# SensorCircuit.net
KiCad netlist of a schematic drawn in Altium Designer
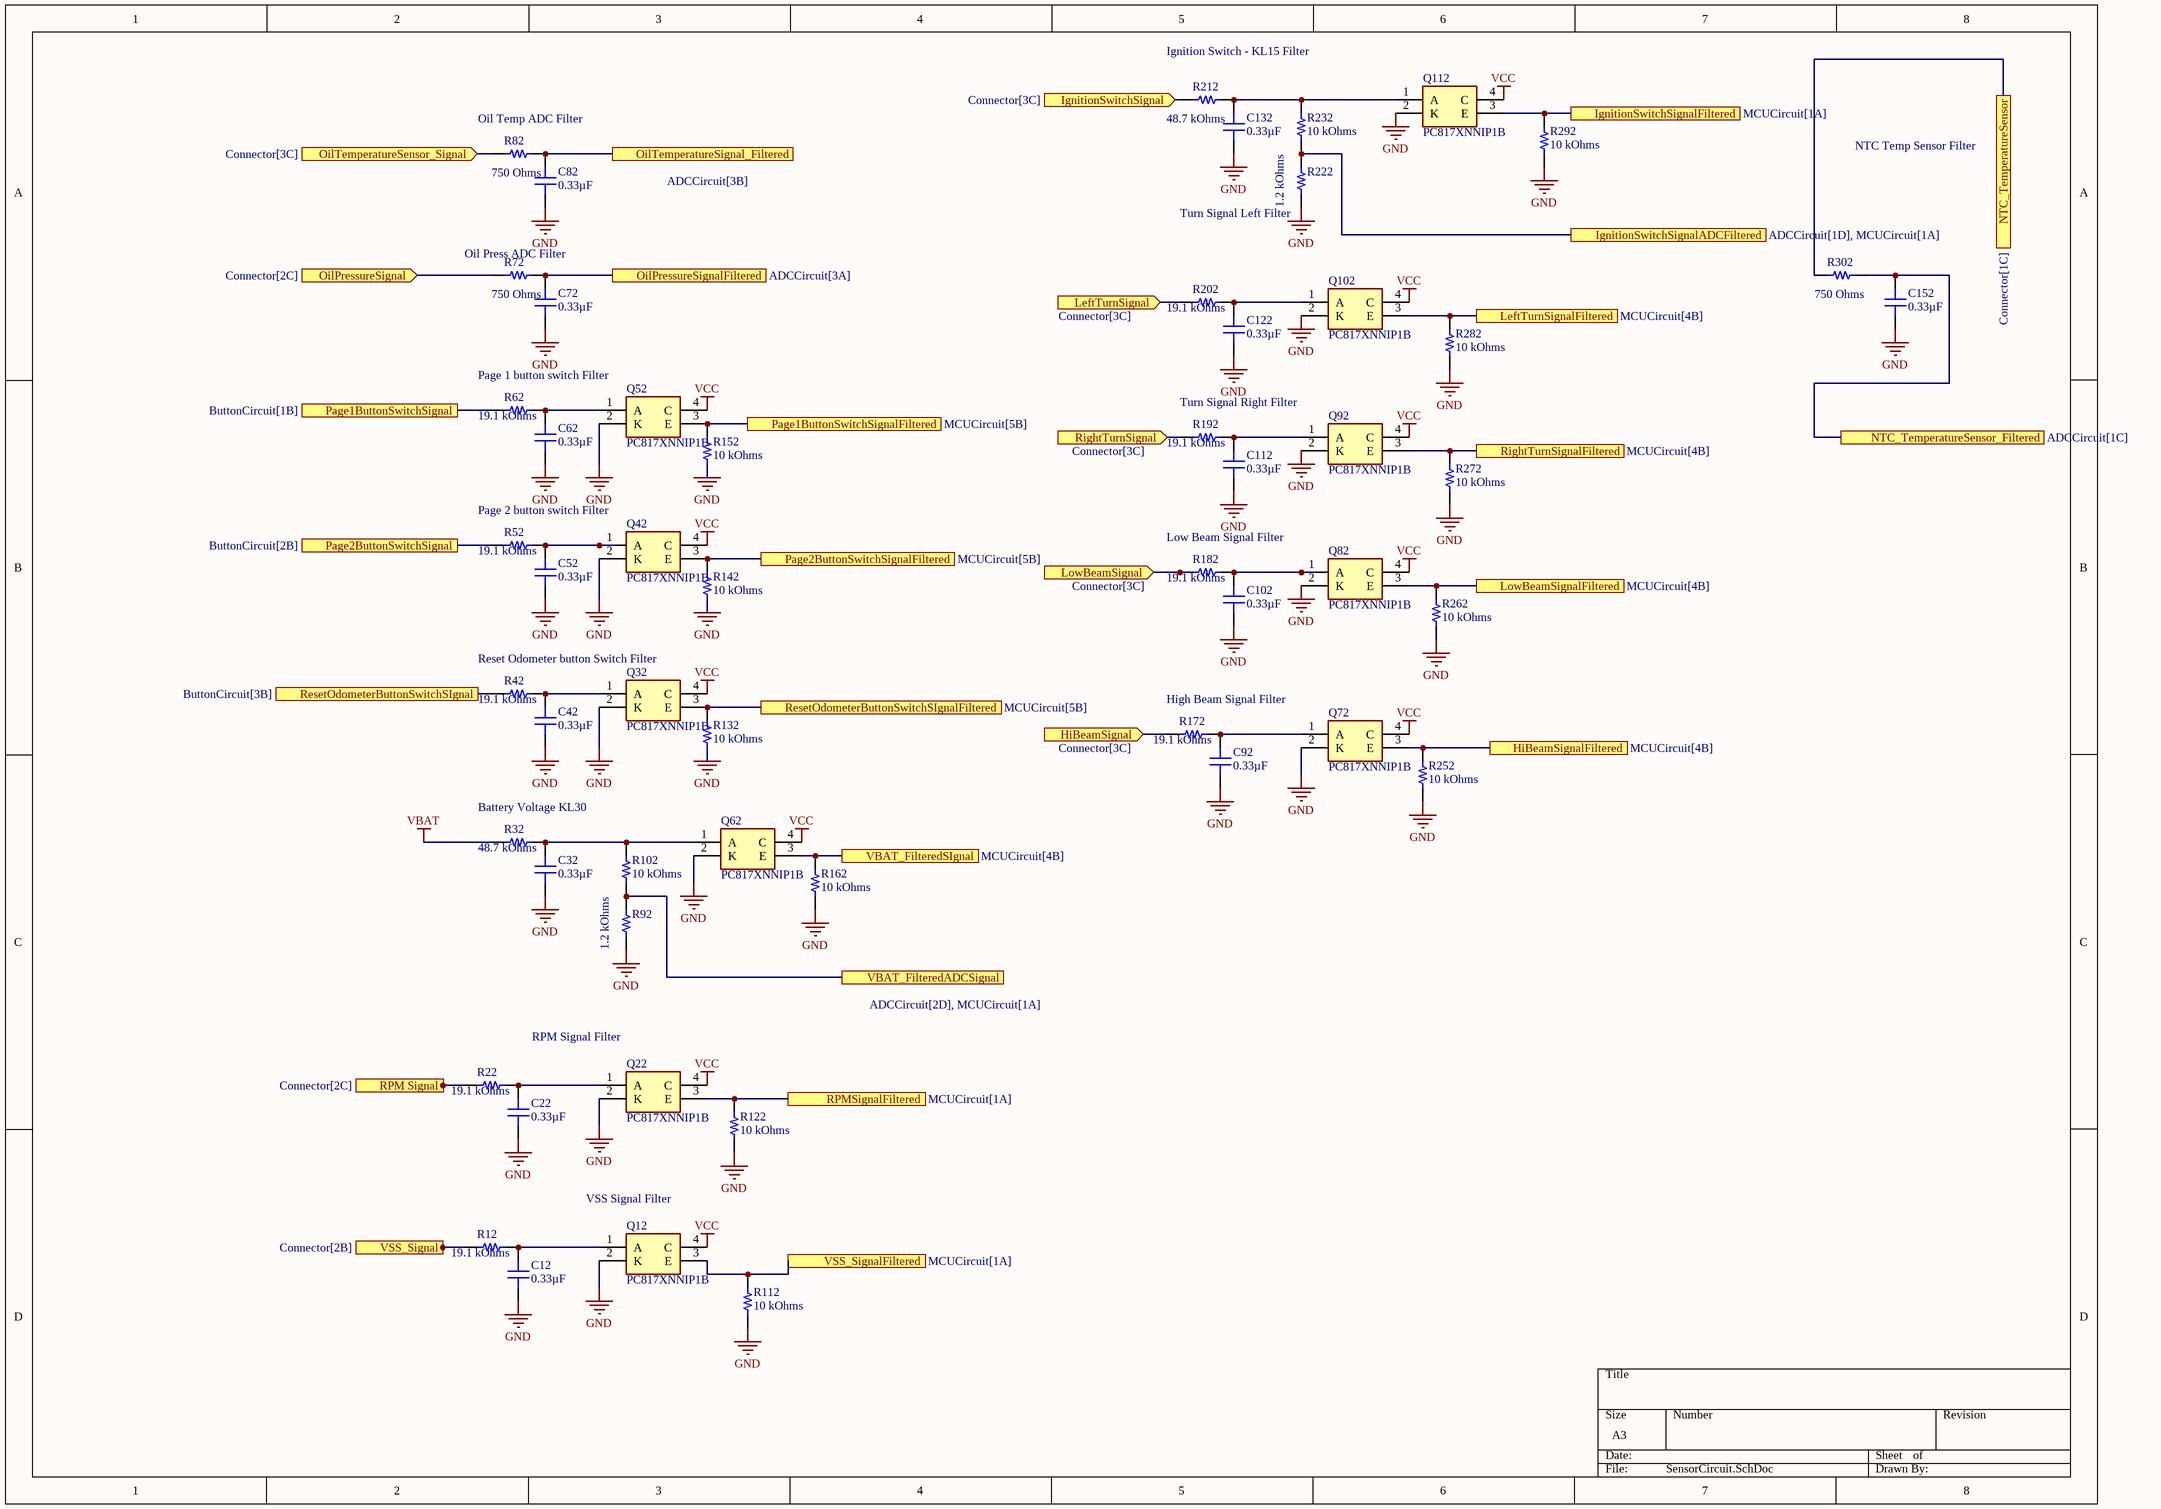
[diagram p0: SensorCircuit.SchDoc]

(export (version "E")
  (design (tool "Eeschema 10.0.6"))
  (components
    (comp (ref "C12")
      (value "0.33µF")
      (footprint "C0805")
      (description "CAP CER 0.33UF 16V X7R 0805")
      (fields (field (name "PART NUMBER") "0805YC334JAT2A") (field (name "MANUFACTURER") "AVX Corporation"))
      (libsource (lib "Celestial Altium Library - altium_library") (part "Capacitor"))
    )
    (comp (ref "C22")
      (value "0.33µF")
      (footprint "C0805")
      (description "CAP CER 0.33UF 16V X7R 0805")
      (fields (field (name "PART NUMBER") "0805YC334JAT2A") (field (name "MANUFACTURER") "AVX Corporation"))
      (libsource (lib "Celestial Altium Library - altium_library") (part "Capacitor"))
    )
    (comp (ref "C32")
      (value "0.33µF")
      (footprint "C0805")
      (description "CAP CER 0.33UF 16V X7R 0805")
      (fields (field (name "PART NUMBER") "0805YC334JAT2A") (field (name "MANUFACTURER") "AVX Corporation"))
      (libsource (lib "Celestial Altium Library - altium_library") (part "Capacitor"))
    )
    (comp (ref "C42")
      (value "0.33µF")
      (footprint "C0805")
      (description "CAP CER 0.33UF 16V X7R 0805")
      (fields (field (name "PART NUMBER") "0805YC334JAT2A") (field (name "MANUFACTURER") "AVX Corporation"))
      (libsource (lib "Celestial Altium Library - altium_library") (part "Capacitor"))
    )
    (comp (ref "C52")
      (value "0.33µF")
      (footprint "C0805")
      (description "CAP CER 0.33UF 16V X7R 0805")
      (fields (field (name "PART NUMBER") "0805YC334JAT2A") (field (name "MANUFACTURER") "AVX Corporation"))
      (libsource (lib "Celestial Altium Library - altium_library") (part "Capacitor"))
    )
    (comp (ref "C62")
      (value "0.33µF")
      (footprint "C0805")
      (description "CAP CER 0.33UF 16V X7R 0805")
      (fields (field (name "PART NUMBER") "0805YC334JAT2A") (field (name "MANUFACTURER") "AVX Corporation"))
      (libsource (lib "Celestial Altium Library - altium_library") (part "Capacitor"))
    )
    (comp (ref "C72")
      (value "0.33µF")
      (footprint "C0805")
      (description "CAP CER 0.33UF 16V X7R 0805")
      (fields (field (name "PART NUMBER") "0805YC334JAT2A") (field (name "MANUFACTURER") "AVX Corporation"))
      (libsource (lib "Celestial Altium Library - altium_library") (part "Capacitor"))
    )
    (comp (ref "C82")
      (value "0.33µF")
      (footprint "C0805")
      (description "CAP CER 0.33UF 16V X7R 0805")
      (fields (field (name "PART NUMBER") "0805YC334JAT2A") (field (name "MANUFACTURER") "AVX Corporation"))
      (libsource (lib "Celestial Altium Library - altium_library") (part "Capacitor"))
    )
    (comp (ref "C92")
      (value "0.33µF")
      (footprint "C0805")
      (description "CAP CER 0.33UF 16V X7R 0805")
      (fields (field (name "PART NUMBER") "0805YC334JAT2A") (field (name "MANUFACTURER") "AVX Corporation"))
      (libsource (lib "Celestial Altium Library - altium_library") (part "Capacitor"))
    )
    (comp (ref "C102")
      (value "0.33µF")
      (footprint "C0805")
      (description "CAP CER 0.33UF 16V X7R 0805")
      (fields (field (name "PART NUMBER") "0805YC334JAT2A") (field (name "MANUFACTURER") "AVX Corporation"))
      (libsource (lib "Celestial Altium Library - altium_library") (part "Capacitor"))
    )
    (comp (ref "C112")
      (value "0.33µF")
      (footprint "C0805")
      (description "CAP CER 0.33UF 16V X7R 0805")
      (fields (field (name "PART NUMBER") "0805YC334JAT2A") (field (name "MANUFACTURER") "AVX Corporation"))
      (libsource (lib "Celestial Altium Library - altium_library") (part "Capacitor"))
    )
    (comp (ref "C122")
      (value "0.33µF")
      (footprint "C0805")
      (description "CAP CER 0.33UF 16V X7R 0805")
      (fields (field (name "PART NUMBER") "0805YC334JAT2A") (field (name "MANUFACTURER") "AVX Corporation"))
      (libsource (lib "Celestial Altium Library - altium_library") (part "Capacitor"))
    )
    (comp (ref "C132")
      (value "0.33µF")
      (footprint "C0805")
      (description "CAP CER 0.33UF 16V X7R 0805")
      (fields (field (name "PART NUMBER") "0805YC334JAT2A") (field (name "MANUFACTURER") "AVX Corporation"))
      (libsource (lib "Celestial Altium Library - altium_library") (part "Capacitor"))
    )
    (comp (ref "C152")
      (value "0.33µF")
      (footprint "C0805")
      (description "CAP CER 0.33UF 16V X7R 0805")
      (fields (field (name "PART NUMBER") "0805YC334JAT2A") (field (name "MANUFACTURER") "AVX Corporation"))
      (libsource (lib "Celestial Altium Library - altium_library") (part "Capacitor"))
    )
    (comp (ref "Q12")
      (value "PC817XNNIP1B")
      (footprint "SamacSys:SOP254P960X420-4N")
      (description "Phototransistor")
      (fields (field (name "MOUSER PART NUMBER") "852-PC817XNNIP1B"))
      (libsource (lib "*") (part "PC817XNNIP1B"))
    )
    (comp (ref "Q22")
      (value "PC817XNNIP1B")
      (footprint "SamacSys:SOP254P960X420-4N")
      (description "Phototransistor")
      (fields (field (name "MOUSER PART NUMBER") "852-PC817XNNIP1B"))
      (libsource (lib "*") (part "PC817XNNIP1B"))
    )
    (comp (ref "Q32")
      (value "PC817XNNIP1B")
      (footprint "SamacSys:SOP254P960X420-4N")
      (description "Phototransistor")
      (fields (field (name "MOUSER PART NUMBER") "852-PC817XNNIP1B"))
      (libsource (lib "*") (part "PC817XNNIP1B"))
    )
    (comp (ref "Q42")
      (value "PC817XNNIP1B")
      (footprint "SamacSys:SOP254P960X420-4N")
      (description "Phototransistor")
      (fields (field (name "MOUSER PART NUMBER") "852-PC817XNNIP1B"))
      (libsource (lib "*") (part "PC817XNNIP1B"))
    )
    (comp (ref "Q52")
      (value "PC817XNNIP1B")
      (footprint "SamacSys:SOP254P960X420-4N")
      (description "Phototransistor")
      (fields (field (name "MOUSER PART NUMBER") "852-PC817XNNIP1B"))
      (libsource (lib "*") (part "PC817XNNIP1B"))
    )
    (comp (ref "Q62")
      (value "PC817XNNIP1B")
      (footprint "SamacSys:SOP254P960X420-4N")
      (description "Phototransistor")
      (fields (field (name "MOUSER PART NUMBER") "852-PC817XNNIP1B"))
      (libsource (lib "*") (part "PC817XNNIP1B"))
    )
    (comp (ref "Q72")
      (value "PC817XNNIP1B")
      (footprint "SamacSys:SOP254P960X420-4N")
      (description "Phototransistor")
      (fields (field (name "MOUSER PART NUMBER") "852-PC817XNNIP1B"))
      (libsource (lib "*") (part "PC817XNNIP1B"))
    )
    (comp (ref "Q82")
      (value "PC817XNNIP1B")
      (footprint "SamacSys:SOP254P960X420-4N")
      (description "Phototransistor")
      (fields (field (name "MOUSER PART NUMBER") "852-PC817XNNIP1B"))
      (libsource (lib "*") (part "PC817XNNIP1B"))
    )
    (comp (ref "Q92")
      (value "PC817XNNIP1B")
      (footprint "SamacSys:SOP254P960X420-4N")
      (description "Phototransistor")
      (fields (field (name "MOUSER PART NUMBER") "852-PC817XNNIP1B"))
      (libsource (lib "*") (part "PC817XNNIP1B"))
    )
    (comp (ref "Q102")
      (value "PC817XNNIP1B")
      (footprint "SamacSys:SOP254P960X420-4N")
      (description "Phototransistor")
      (fields (field (name "MOUSER PART NUMBER") "852-PC817XNNIP1B"))
      (libsource (lib "*") (part "PC817XNNIP1B"))
    )
    (comp (ref "Q112")
      (value "PC817XNNIP1B")
      (footprint "SamacSys:SOP254P960X420-4N")
      (description "Phototransistor")
      (fields (field (name "MOUSER PART NUMBER") "852-PC817XNNIP1B"))
      (libsource (lib "*") (part "PC817XNNIP1B"))
    )
    (comp (ref "R12")
      (value "19.1 kOhms")
      (footprint "RES 0805_2012")
      (description "RES SMD 19.1K OHM 1% 1/8W 0805")
      (fields (field (name "PART NUMBER") "CRCW080519K1FKEA") (field (name "MANUFACTURER") "Vishay Dale"))
      (libsource (lib "Celestial Altium Library - altium_library") (part "Resistor"))
    )
    (comp (ref "R22")
      (value "19.1 kOhms")
      (footprint "RES 0805_2012")
      (description "RES SMD 19.1K OHM 1% 1/8W 0805")
      (fields (field (name "PART NUMBER") "CRCW080519K1FKEA") (field (name "MANUFACTURER") "Vishay Dale"))
      (libsource (lib "Celestial Altium Library - altium_library") (part "Resistor"))
    )
    (comp (ref "R32")
      (value "48.7 kOhms")
      (footprint "RES 0805_2012")
      (description "RES SMD 48.7K OHM 1% 1/8W 0805")
      (fields (field (name "PART NUMBER") "CRCW080548K7FKEA") (field (name "MANUFACTURER") "Vishay Dale"))
      (libsource (lib "Celestial Altium Library - altium_library") (part "Resistor"))
    )
    (comp (ref "R42")
      (value "19.1 kOhms")
      (footprint "RES 0805_2012")
      (description "RES SMD 19.1K OHM 1% 1/8W 0805")
      (fields (field (name "PART NUMBER") "CRCW080519K1FKEA") (field (name "MANUFACTURER") "Vishay Dale"))
      (libsource (lib "Celestial Altium Library - altium_library") (part "Resistor"))
    )
    (comp (ref "R52")
      (value "19.1 kOhms")
      (footprint "RES 0805_2012")
      (description "RES SMD 19.1K OHM 1% 1/8W 0805")
      (fields (field (name "PART NUMBER") "CRCW080519K1FKEA") (field (name "MANUFACTURER") "Vishay Dale"))
      (libsource (lib "Celestial Altium Library - altium_library") (part "Resistor"))
    )
    (comp (ref "R62")
      (value "19.1 kOhms")
      (footprint "RES 0805_2012")
      (description "RES SMD 19.1K OHM 1% 1/8W 0805")
      (fields (field (name "PART NUMBER") "CRCW080519K1FKEA") (field (name "MANUFACTURER") "Vishay Dale"))
      (libsource (lib "Celestial Altium Library - altium_library") (part "Resistor"))
    )
    (comp (ref "R72")
      (value "750 Ohms")
      (footprint "RES 0805_2012")
      (description "RES 750 OHM 0.1% 1/8W 0805")
      (fields
        (field (name "PART NUMBER") "RNCF0805BTE750R")
        (field (name "MANUFACTURER") "Stackpole Electronics Inc")
      )
      (libsource (lib "Celestial Altium Library - altium_library") (part "Resistor"))
    )
    (comp (ref "R82")
      (value "750 Ohms")
      (footprint "RES 0805_2012")
      (description "RES 750 OHM 0.1% 1/8W 0805")
      (fields
        (field (name "PART NUMBER") "RNCF0805BTE750R")
        (field (name "MANUFACTURER") "Stackpole Electronics Inc")
      )
      (libsource (lib "Celestial Altium Library - altium_library") (part "Resistor"))
    )
    (comp (ref "R92")
      (value "1.2 kOhms")
      (footprint "RES 0805_2012")
      (description "RES SMD 1.2K OHM 0.1% 1/10W 0805")
      (fields
        (field (name "PART NUMBER") "CPF0805B1K2E1")
        (field (name "MANUFACTURER") "TE Connectivity Passive Product")
      )
      (libsource (lib "Celestial Altium Library - altium_library") (part "Resistor"))
    )
    (comp (ref "R102")
      (value "10 kOhms")
      (footprint "RES 0805_2012")
      (description "RES 10K OHM 0.1% 1/5W 0805")
      (fields
        (field (name "PART NUMBER") "9-2176375-1")
        (field (name "MANUFACTURER") "TE Connectivity Passive Product")
      )
      (libsource (lib "Celestial Altium Library - altium_library") (part "Resistor"))
    )
    (comp (ref "R112")
      (value "10 kOhms")
      (footprint "RES 0805_2012")
      (description "3430 A2 1% 10K 100PPM 1K RL")
      (fields
        (field (name "PART NUMBER") "3430A2F10KTDF")
        (field (name "MANUFACTURER") "TE Connectivity Passive Product")
      )
      (libsource (lib "Celestial Altium Library - altium_library") (part "Resistor"))
    )
    (comp (ref "R122")
      (value "10 kOhms")
      (footprint "RES 0805_2012")
      (description "3430 A2 1% 10K 100PPM 1K RL")
      (fields
        (field (name "PART NUMBER") "3430A2F10KTDF")
        (field (name "MANUFACTURER") "TE Connectivity Passive Product")
      )
      (libsource (lib "Celestial Altium Library - altium_library") (part "Resistor"))
    )
    (comp (ref "R132")
      (value "10 kOhms")
      (footprint "RES 0805_2012")
      (description "3430 A2 1% 10K 100PPM 1K RL")
      (fields
        (field (name "PART NUMBER") "3430A2F10KTDF")
        (field (name "MANUFACTURER") "TE Connectivity Passive Product")
      )
      (libsource (lib "Celestial Altium Library - altium_library") (part "Resistor"))
    )
    (comp (ref "R142")
      (value "10 kOhms")
      (footprint "RES 0805_2012")
      (description "3430 A2 1% 10K 100PPM 1K RL")
      (fields
        (field (name "PART NUMBER") "3430A2F10KTDF")
        (field (name "MANUFACTURER") "TE Connectivity Passive Product")
      )
      (libsource (lib "Celestial Altium Library - altium_library") (part "Resistor"))
    )
    (comp (ref "R152")
      (value "10 kOhms")
      (footprint "RES 0805_2012")
      (description "3430 A2 1% 10K 100PPM 1K RL")
      (fields
        (field (name "PART NUMBER") "3430A2F10KTDF")
        (field (name "MANUFACTURER") "TE Connectivity Passive Product")
      )
      (libsource (lib "Celestial Altium Library - altium_library") (part "Resistor"))
    )
    (comp (ref "R162")
      (value "10 kOhms")
      (footprint "RES 0805_2012")
      (description "3430 A2 1% 10K 100PPM 1K RL")
      (fields
        (field (name "PART NUMBER") "3430A2F10KTDF")
        (field (name "MANUFACTURER") "TE Connectivity Passive Product")
      )
      (libsource (lib "Celestial Altium Library - altium_library") (part "Resistor"))
    )
    (comp (ref "R172")
      (value "19.1 kOhms")
      (footprint "RES 0805_2012")
      (description "RES SMD 19.1K OHM 1% 1/8W 0805")
      (fields (field (name "PART NUMBER") "CRCW080519K1FKEA") (field (name "MANUFACTURER") "Vishay Dale"))
      (libsource (lib "Celestial Altium Library - altium_library") (part "Resistor"))
    )
    (comp (ref "R182")
      (value "19.1 kOhms")
      (footprint "RES 0805_2012")
      (description "RES SMD 19.1K OHM 1% 1/8W 0805")
      (fields (field (name "PART NUMBER") "CRCW080519K1FKEA") (field (name "MANUFACTURER") "Vishay Dale"))
      (libsource (lib "Celestial Altium Library - altium_library") (part "Resistor"))
    )
    (comp (ref "R192")
      (value "19.1 kOhms")
      (footprint "RES 0805_2012")
      (description "RES SMD 19.1K OHM 1% 1/8W 0805")
      (fields (field (name "PART NUMBER") "CRCW080519K1FKEA") (field (name "MANUFACTURER") "Vishay Dale"))
      (libsource (lib "Celestial Altium Library - altium_library") (part "Resistor"))
    )
    (comp (ref "R202")
      (value "19.1 kOhms")
      (footprint "RES 0805_2012")
      (description "RES SMD 19.1K OHM 1% 1/8W 0805")
      (fields (field (name "PART NUMBER") "CRCW080519K1FKEA") (field (name "MANUFACTURER") "Vishay Dale"))
      (libsource (lib "Celestial Altium Library - altium_library") (part "Resistor"))
    )
    (comp (ref "R212")
      (value "48.7 kOhms")
      (footprint "RES 0805_2012")
      (description "RES SMD 48.7K OHM 1% 1/8W 0805")
      (fields (field (name "PART NUMBER") "CRCW080548K7FKEA") (field (name "MANUFACTURER") "Vishay Dale"))
      (libsource (lib "Celestial Altium Library - altium_library") (part "Resistor"))
    )
    (comp (ref "R222")
      (value "1.2 kOhms")
      (footprint "RES 0805_2012")
      (description "RES SMD 1.2K OHM 0.1% 1/10W 0805")
      (fields
        (field (name "PART NUMBER") "CPF0805B1K2E1")
        (field (name "MANUFACTURER") "TE Connectivity Passive Product")
      )
      (libsource (lib "Celestial Altium Library - altium_library") (part "Resistor"))
    )
    (comp (ref "R232")
      (value "10 kOhms")
      (footprint "RES 0805_2012")
      (description "RES 10K OHM 0.1% 1/5W 0805")
      (fields
        (field (name "PART NUMBER") "9-2176375-1")
        (field (name "MANUFACTURER") "TE Connectivity Passive Product")
      )
      (libsource (lib "Celestial Altium Library - altium_library") (part "Resistor"))
    )
    (comp (ref "R252")
      (value "10 kOhms")
      (footprint "RES 0805_2012")
      (description "3430 A2 1% 10K 100PPM 1K RL")
      (fields
        (field (name "PART NUMBER") "3430A2F10KTDF")
        (field (name "MANUFACTURER") "TE Connectivity Passive Product")
      )
      (libsource (lib "Celestial Altium Library - altium_library") (part "Resistor"))
    )
    (comp (ref "R262")
      (value "10 kOhms")
      (footprint "RES 0805_2012")
      (description "3430 A2 1% 10K 100PPM 1K RL")
      (fields
        (field (name "PART NUMBER") "3430A2F10KTDF")
        (field (name "MANUFACTURER") "TE Connectivity Passive Product")
      )
      (libsource (lib "Celestial Altium Library - altium_library") (part "Resistor"))
    )
    (comp (ref "R272")
      (value "10 kOhms")
      (footprint "RES 0805_2012")
      (description "3430 A2 1% 10K 100PPM 1K RL")
      (fields
        (field (name "PART NUMBER") "3430A2F10KTDF")
        (field (name "MANUFACTURER") "TE Connectivity Passive Product")
      )
      (libsource (lib "Celestial Altium Library - altium_library") (part "Resistor"))
    )
    (comp (ref "R282")
      (value "10 kOhms")
      (footprint "RES 0805_2012")
      (description "3430 A2 1% 10K 100PPM 1K RL")
      (fields
        (field (name "PART NUMBER") "3430A2F10KTDF")
        (field (name "MANUFACTURER") "TE Connectivity Passive Product")
      )
      (libsource (lib "Celestial Altium Library - altium_library") (part "Resistor"))
    )
    (comp (ref "R292")
      (value "10 kOhms")
      (footprint "RES 0805_2012")
      (description "3430 A2 1% 10K 100PPM 1K RL")
      (fields
        (field (name "PART NUMBER") "3430A2F10KTDF")
        (field (name "MANUFACTURER") "TE Connectivity Passive Product")
      )
      (libsource (lib "Celestial Altium Library - altium_library") (part "Resistor"))
    )
    (comp (ref "R302")
      (value "750 Ohms")
      (footprint "RES 0805_2012")
      (description "RES 750 OHM 0.1% 1/8W 0805")
      (fields
        (field (name "PART NUMBER") "RNCF0805BTE750R")
        (field (name "MANUFACTURER") "Stackpole Electronics Inc")
      )
      (libsource (lib "Celestial Altium Library - altium_library") (part "Resistor"))
    )
  )
  (nets
    (net (code "1") (name "/HiBeamSignal") (class "Default")
      (node (ref "R172") (pin "1") (pinfunction "1_1") (pintype "passive"))
    )
    (net (code "2") (name "/HiBeamSignalFiltered") (class "Default")
      (node (ref "Q72") (pin "3") (pinfunction "E_3") (pintype "passive"))
      (node (ref "R252") (pin "2") (pinfunction "2_2") (pintype "passive"))
    )
    (net (code "3") (name "/IgnitionSwitchSignal") (class "Default")
      (node (ref "R212") (pin "1") (pinfunction "1_1") (pintype "passive"))
    )
    (net (code "4") (name "/IgnitionSwitchSignalADCFiltered") (class "Default")
      (node (ref "R222") (pin "2") (pinfunction "2_2") (pintype "passive"))
      (node (ref "R232") (pin "1") (pinfunction "1_1") (pintype "passive"))
    )
    (net (code "5") (name "/IgnitionSwitchSignalFiltered") (class "Default")
      (node (ref "Q112") (pin "3") (pinfunction "E_3") (pintype "passive"))
      (node (ref "R292") (pin "2") (pinfunction "2_2") (pintype "passive"))
    )
    (net (code "6") (name "/LeftTurnSignal") (class "Default")
      (node (ref "R202") (pin "1") (pinfunction "1_1") (pintype "passive"))
    )
    (net (code "7") (name "/LeftTurnSignalFiltered") (class "Default")
      (node (ref "Q102") (pin "3") (pinfunction "E_3") (pintype "passive"))
      (node (ref "R282") (pin "2") (pinfunction "2_2") (pintype "passive"))
    )
    (net (code "8") (name "/LowBeamSignal") (class "Default")
      (node (ref "R182") (pin "1") (pinfunction "1_1") (pintype "passive"))
    )
    (net (code "9") (name "/LowBeamSignalFiltered") (class "Default")
      (node (ref "Q82") (pin "3") (pinfunction "E_3") (pintype "passive"))
      (node (ref "R262") (pin "2") (pinfunction "2_2") (pintype "passive"))
    )
    (net (code "10") (name "/NTC_TemperatureSensor") (class "Default")
      (node (ref "R302") (pin "1") (pinfunction "1_1") (pintype "passive"))
    )
    (net (code "11") (name "/NTC_TemperatureSensor_Filtered") (class "Default")
      (node (ref "C152") (pin "2") (pinfunction "2_2") (pintype "passive"))
      (node (ref "R302") (pin "2") (pinfunction "2_2") (pintype "passive"))
    )
    (net (code "12") (name "/OilPressureSignal") (class "Default")
      (node (ref "R72") (pin "1") (pinfunction "1_1") (pintype "passive"))
    )
    (net (code "13") (name "/OilPressureSignalFiltered") (class "Default")
      (node (ref "C72") (pin "2") (pinfunction "2_2") (pintype "passive"))
      (node (ref "R72") (pin "2") (pinfunction "2_2") (pintype "passive"))
    )
    (net (code "14") (name "/OilTemperatureSensor_Signal") (class "Default")
      (node (ref "R82") (pin "1") (pinfunction "1_1") (pintype "passive"))
    )
    (net (code "15") (name "/OilTemperatureSignal_Filtered") (class "Default")
      (node (ref "C82") (pin "2") (pinfunction "2_2") (pintype "passive"))
      (node (ref "R82") (pin "2") (pinfunction "2_2") (pintype "passive"))
    )
    (net (code "16") (name "/Page1ButtonSwitchSignal") (class "Default")
      (node (ref "R62") (pin "1") (pinfunction "1_1") (pintype "passive"))
    )
    (net (code "17") (name "/Page1ButtonSwitchSignalFiltered") (class "Default")
      (node (ref "Q52") (pin "3") (pinfunction "E_3") (pintype "passive"))
      (node (ref "R152") (pin "2") (pinfunction "2_2") (pintype "passive"))
    )
    (net (code "18") (name "/Page2ButtonSwitchSignal") (class "Default")
      (node (ref "R52") (pin "1") (pinfunction "1_1") (pintype "passive"))
    )
    (net (code "19") (name "/Page2ButtonSwitchSignalFiltered") (class "Default")
      (node (ref "Q42") (pin "3") (pinfunction "E_3") (pintype "passive"))
      (node (ref "R142") (pin "2") (pinfunction "2_2") (pintype "passive"))
    )
    (net (code "20") (name "/RPM Signal") (class "Default")
      (node (ref "R22") (pin "1") (pinfunction "1_1") (pintype "passive"))
    )
    (net (code "21") (name "/RPMSignalFiltered") (class "Default")
      (node (ref "Q22") (pin "3") (pinfunction "E_3") (pintype "passive"))
      (node (ref "R122") (pin "2") (pinfunction "2_2") (pintype "passive"))
    )
    (net (code "22") (name "/ResetOdometerButtonSwitchSIgnal") (class "Default")
      (node (ref "R42") (pin "1") (pinfunction "1_1") (pintype "passive"))
    )
    (net (code "23") (name "/ResetOdometerButtonSwitchSIgnalFiltered") (class "Default")
      (node (ref "Q32") (pin "3") (pinfunction "E_3") (pintype "passive"))
      (node (ref "R132") (pin "2") (pinfunction "2_2") (pintype "passive"))
    )
    (net (code "24") (name "/RightTurnSignal") (class "Default")
      (node (ref "R192") (pin "1") (pinfunction "1_1") (pintype "passive"))
    )
    (net (code "25") (name "/RightTurnSignalFiltered") (class "Default")
      (node (ref "Q92") (pin "3") (pinfunction "E_3") (pintype "passive"))
      (node (ref "R272") (pin "2") (pinfunction "2_2") (pintype "passive"))
    )
    (net (code "26") (name "/VBAT_FilteredADCSignal") (class "Default")
      (node (ref "R102") (pin "1") (pinfunction "1_1") (pintype "passive"))
      (node (ref "R92") (pin "2") (pinfunction "2_2") (pintype "passive"))
    )
    (net (code "27") (name "/VBAT_FilteredSIgnal") (class "Default")
      (node (ref "Q62") (pin "3") (pinfunction "E_3") (pintype "passive"))
      (node (ref "R162") (pin "2") (pinfunction "2_2") (pintype "passive"))
    )
    (net (code "28") (name "/VSS_Signal") (class "Default")
      (node (ref "R12") (pin "1") (pinfunction "1_1") (pintype "passive"))
    )
    (net (code "29") (name "/VSS_SignalFiltered") (class "Default")
      (node (ref "Q12") (pin "3") (pinfunction "E_3") (pintype "passive"))
      (node (ref "R112") (pin "2") (pinfunction "2_2") (pintype "passive"))
    )
    (net (code "30") (name "GND") (class "Default")
      (node (ref "C102") (pin "1") (pinfunction "1_1") (pintype "passive"))
      (node (ref "C112") (pin "1") (pinfunction "1_1") (pintype "passive"))
      (node (ref "C12") (pin "1") (pinfunction "1_1") (pintype "passive"))
      (node (ref "C122") (pin "1") (pinfunction "1_1") (pintype "passive"))
      (node (ref "C132") (pin "1") (pinfunction "1_1") (pintype "passive"))
      (node (ref "C152") (pin "1") (pinfunction "1_1") (pintype "passive"))
      (node (ref "C22") (pin "1") (pinfunction "1_1") (pintype "passive"))
      (node (ref "C32") (pin "1") (pinfunction "1_1") (pintype "passive"))
      (node (ref "C42") (pin "1") (pinfunction "1_1") (pintype "passive"))
      (node (ref "C52") (pin "1") (pinfunction "1_1") (pintype "passive"))
      (node (ref "C62") (pin "1") (pinfunction "1_1") (pintype "passive"))
      (node (ref "C72") (pin "1") (pinfunction "1_1") (pintype "passive"))
      (node (ref "C82") (pin "1") (pinfunction "1_1") (pintype "passive"))
      (node (ref "C92") (pin "1") (pinfunction "1_1") (pintype "passive"))
      (node (ref "Q102") (pin "2") (pinfunction "K_2") (pintype "passive"))
      (node (ref "Q112") (pin "2") (pinfunction "K_2") (pintype "passive"))
      (node (ref "Q12") (pin "2") (pinfunction "K_2") (pintype "passive"))
      (node (ref "Q22") (pin "2") (pinfunction "K_2") (pintype "passive"))
      (node (ref "Q32") (pin "2") (pinfunction "K_2") (pintype "passive"))
      (node (ref "Q42") (pin "2") (pinfunction "K_2") (pintype "passive"))
      (node (ref "Q52") (pin "2") (pinfunction "K_2") (pintype "passive"))
      (node (ref "Q62") (pin "2") (pinfunction "K_2") (pintype "passive"))
      (node (ref "Q72") (pin "2") (pinfunction "K_2") (pintype "passive"))
      (node (ref "Q82") (pin "2") (pinfunction "K_2") (pintype "passive"))
      (node (ref "Q92") (pin "2") (pinfunction "K_2") (pintype "passive"))
      (node (ref "R112") (pin "1") (pinfunction "1_1") (pintype "passive"))
      (node (ref "R122") (pin "1") (pinfunction "1_1") (pintype "passive"))
      (node (ref "R132") (pin "1") (pinfunction "1_1") (pintype "passive"))
      (node (ref "R142") (pin "1") (pinfunction "1_1") (pintype "passive"))
      (node (ref "R152") (pin "1") (pinfunction "1_1") (pintype "passive"))
      (node (ref "R162") (pin "1") (pinfunction "1_1") (pintype "passive"))
      (node (ref "R222") (pin "1") (pinfunction "1_1") (pintype "passive"))
      (node (ref "R252") (pin "1") (pinfunction "1_1") (pintype "passive"))
      (node (ref "R262") (pin "1") (pinfunction "1_1") (pintype "passive"))
      (node (ref "R272") (pin "1") (pinfunction "1_1") (pintype "passive"))
      (node (ref "R282") (pin "1") (pinfunction "1_1") (pintype "passive"))
      (node (ref "R292") (pin "1") (pinfunction "1_1") (pintype "passive"))
      (node (ref "R92") (pin "1") (pinfunction "1_1") (pintype "passive"))
    )
    (net (code "31") (name "Net-(Q12-A)") (class "Default")
      (node (ref "C12") (pin "2") (pinfunction "2_2") (pintype "passive"))
      (node (ref "Q12") (pin "1") (pinfunction "A_1") (pintype "passive"))
      (node (ref "R12") (pin "2") (pinfunction "2_2") (pintype "passive"))
    )
    (net (code "32") (name "Net-(Q22-A)") (class "Default")
      (node (ref "C22") (pin "2") (pinfunction "2_2") (pintype "passive"))
      (node (ref "Q22") (pin "1") (pinfunction "A_1") (pintype "passive"))
      (node (ref "R22") (pin "2") (pinfunction "2_2") (pintype "passive"))
    )
    (net (code "33") (name "Net-(Q32-A)") (class "Default")
      (node (ref "C42") (pin "2") (pinfunction "2_2") (pintype "passive"))
      (node (ref "Q32") (pin "1") (pinfunction "A_1") (pintype "passive"))
      (node (ref "R42") (pin "2") (pinfunction "2_2") (pintype "passive"))
    )
    (net (code "34") (name "Net-(Q42-A)") (class "Default")
      (node (ref "C52") (pin "2") (pinfunction "2_2") (pintype "passive"))
      (node (ref "Q42") (pin "1") (pinfunction "A_1") (pintype "passive"))
      (node (ref "R52") (pin "2") (pinfunction "2_2") (pintype "passive"))
    )
    (net (code "35") (name "Net-(Q52-A)") (class "Default")
      (node (ref "C62") (pin "2") (pinfunction "2_2") (pintype "passive"))
      (node (ref "Q52") (pin "1") (pinfunction "A_1") (pintype "passive"))
      (node (ref "R62") (pin "2") (pinfunction "2_2") (pintype "passive"))
    )
    (net (code "36") (name "Net-(Q62-A)") (class "Default")
      (node (ref "C32") (pin "2") (pinfunction "2_2") (pintype "passive"))
      (node (ref "Q62") (pin "1") (pinfunction "A_1") (pintype "passive"))
      (node (ref "R102") (pin "2") (pinfunction "2_2") (pintype "passive"))
      (node (ref "R32") (pin "2") (pinfunction "2_2") (pintype "passive"))
    )
    (net (code "37") (name "Net-(Q72-A)") (class "Default")
      (node (ref "C92") (pin "2") (pinfunction "2_2") (pintype "passive"))
      (node (ref "Q72") (pin "1") (pinfunction "A_1") (pintype "passive"))
      (node (ref "R172") (pin "2") (pinfunction "2_2") (pintype "passive"))
    )
    (net (code "38") (name "Net-(Q82-A)") (class "Default")
      (node (ref "C102") (pin "2") (pinfunction "2_2") (pintype "passive"))
      (node (ref "Q82") (pin "1") (pinfunction "A_1") (pintype "passive"))
      (node (ref "R182") (pin "2") (pinfunction "2_2") (pintype "passive"))
    )
    (net (code "39") (name "Net-(Q92-A)") (class "Default")
      (node (ref "C112") (pin "2") (pinfunction "2_2") (pintype "passive"))
      (node (ref "Q92") (pin "1") (pinfunction "A_1") (pintype "passive"))
      (node (ref "R192") (pin "2") (pinfunction "2_2") (pintype "passive"))
    )
    (net (code "40") (name "Net-(Q102-A)") (class "Default")
      (node (ref "C122") (pin "2") (pinfunction "2_2") (pintype "passive"))
      (node (ref "Q102") (pin "1") (pinfunction "A_1") (pintype "passive"))
      (node (ref "R202") (pin "2") (pinfunction "2_2") (pintype "passive"))
    )
    (net (code "41") (name "Net-(Q112-A)") (class "Default")
      (node (ref "C132") (pin "2") (pinfunction "2_2") (pintype "passive"))
      (node (ref "Q112") (pin "1") (pinfunction "A_1") (pintype "passive"))
      (node (ref "R212") (pin "2") (pinfunction "2_2") (pintype "passive"))
      (node (ref "R232") (pin "2") (pinfunction "2_2") (pintype "passive"))
    )
    (net (code "42") (name "VBAT") (class "Default")
      (node (ref "R32") (pin "1") (pinfunction "1_1") (pintype "passive"))
    )
    (net (code "43") (name "VCC") (class "Default")
      (node (ref "Q102") (pin "4") (pinfunction "C_4") (pintype "passive"))
      (node (ref "Q112") (pin "4") (pinfunction "C_4") (pintype "passive"))
      (node (ref "Q12") (pin "4") (pinfunction "C_4") (pintype "passive"))
      (node (ref "Q22") (pin "4") (pinfunction "C_4") (pintype "passive"))
      (node (ref "Q32") (pin "4") (pinfunction "C_4") (pintype "passive"))
      (node (ref "Q42") (pin "4") (pinfunction "C_4") (pintype "passive"))
      (node (ref "Q52") (pin "4") (pinfunction "C_4") (pintype "passive"))
      (node (ref "Q62") (pin "4") (pinfunction "C_4") (pintype "passive"))
      (node (ref "Q72") (pin "4") (pinfunction "C_4") (pintype "passive"))
      (node (ref "Q82") (pin "4") (pinfunction "C_4") (pintype "passive"))
      (node (ref "Q92") (pin "4") (pinfunction "C_4") (pintype "passive"))
    )
  )
)
